# 5_Digitrol.net
KiCad netlist of a schematic drawn in Altium Designer
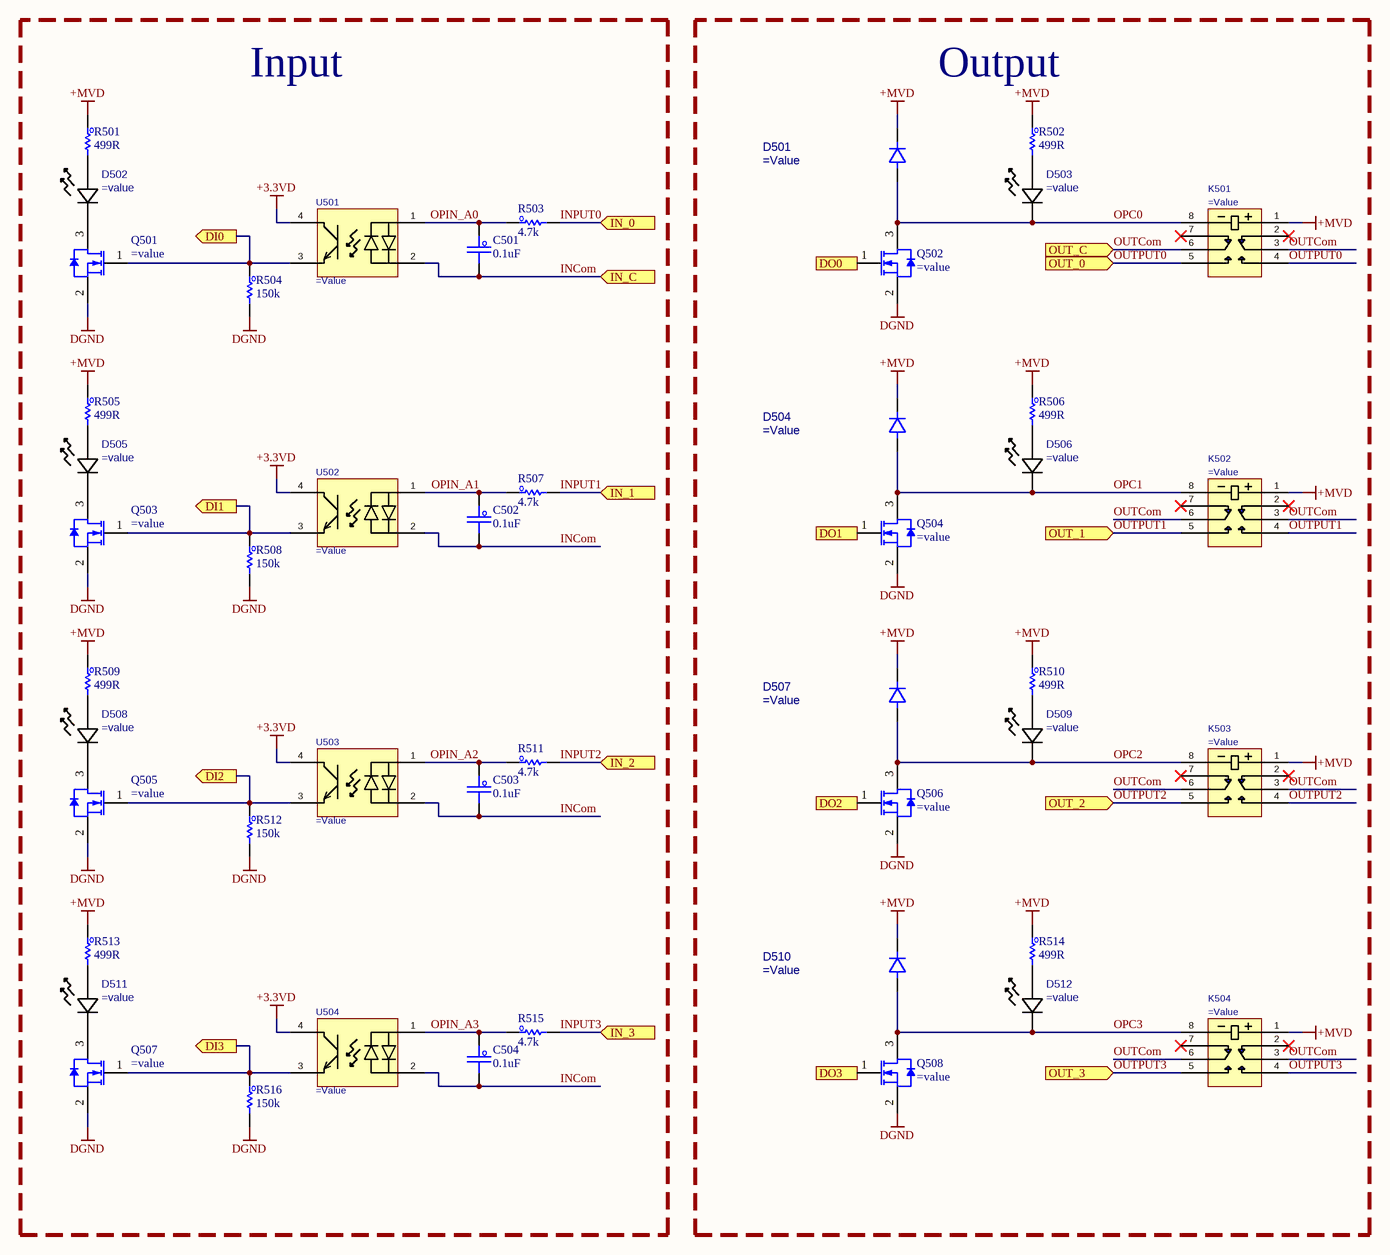
[diagram p0: 5_Digitrol.SchDoc]

(export (version "E")
  (design (tool "Eeschema 10.0.6"))
  (components
    (comp (ref "C501")
      (value "0.1uF")
      (footprint "C_0603")
      (description "CAP CER 0.1UF 50V X7R 0603")
      (fields (field (name "MANUFACTURER") "KEMET") (field (name "PARTNUMBER") "C0603C104K5RACTU"))
      (libsource (lib "UUSymbol") (part "C_Capacitor"))
    )
    (comp (ref "C502")
      (value "0.1uF")
      (footprint "C_0603")
      (description "CAP CER 0.1UF 50V X7R 0603")
      (fields (field (name "MANUFACTURER") "KEMET") (field (name "PARTNUMBER") "C0603C104K5RACTU"))
      (libsource (lib "UUSymbol") (part "C_Capacitor"))
    )
    (comp (ref "C503")
      (value "0.1uF")
      (footprint "C_0603")
      (description "CAP CER 0.1UF 50V X7R 0603")
      (fields (field (name "MANUFACTURER") "KEMET") (field (name "PARTNUMBER") "C0603C104K5RACTU"))
      (libsource (lib "UUSymbol") (part "C_Capacitor"))
    )
    (comp (ref "C504")
      (value "0.1uF")
      (footprint "C_0603")
      (description "CAP CER 0.1UF 50V X7R 0603")
      (fields (field (name "MANUFACTURER") "KEMET") (field (name "PARTNUMBER") "C0603C104K5RACTU"))
      (libsource (lib "UUSymbol") (part "C_Capacitor"))
    )
    (comp (ref "D501")
      (value "~")
      (footprint "DFN119P160X30-2M")
      (description "DIODE SCHOTTKY 30V 2A 0603")
      (fields
        (field (name "MANUFACTURER") "Vishay General Semiconductor - Diodes Division")
        (field (name "PARTNUMBER") "VSKY20301608-G4-08")
      )
      (libsource (lib "UUSymbol") (part "D_PW_VSKY20301608"))
    )
    (comp (ref "D502")
      (value "~")
      (footprint "LED_0VS75000_WRE")
      (description "LED BLUE CLEAR 0603 SMD")
      (fields (field (name "MANUFACTURER") "Wurth Electronics") (field (name "PARTNUMBER") "150060VS75000"))
      (libsource (lib "UUSymbol") (part "D_LED_150060BS75000"))
    )
    (comp (ref "D503")
      (value "~")
      (footprint "LED_0VS75000_WRE")
      (description "LED BLUE CLEAR 0603 SMD")
      (fields (field (name "MANUFACTURER") "Wurth Electronics") (field (name "PARTNUMBER") "150060VS75000"))
      (libsource (lib "UUSymbol") (part "D_LED_150060BS75000"))
    )
    (comp (ref "D504")
      (value "~")
      (footprint "DFN119P160X30-2M")
      (description "DIODE SCHOTTKY 30V 2A 0603")
      (fields
        (field (name "MANUFACTURER") "Vishay General Semiconductor - Diodes Division")
        (field (name "PARTNUMBER") "VSKY20301608-G4-08")
      )
      (libsource (lib "UUSymbol") (part "D_PW_VSKY20301608"))
    )
    (comp (ref "D505")
      (value "~")
      (footprint "LED_0VS75000_WRE")
      (description "LED BLUE CLEAR 0603 SMD")
      (fields (field (name "MANUFACTURER") "Wurth Electronics") (field (name "PARTNUMBER") "150060VS75000"))
      (libsource (lib "UUSymbol") (part "D_LED_150060BS75000"))
    )
    (comp (ref "D506")
      (value "~")
      (footprint "LED_0VS75000_WRE")
      (description "LED BLUE CLEAR 0603 SMD")
      (fields (field (name "MANUFACTURER") "Wurth Electronics") (field (name "PARTNUMBER") "150060VS75000"))
      (libsource (lib "UUSymbol") (part "D_LED_150060BS75000"))
    )
    (comp (ref "D507")
      (value "~")
      (footprint "DFN119P160X30-2M")
      (description "DIODE SCHOTTKY 30V 2A 0603")
      (fields
        (field (name "MANUFACTURER") "Vishay General Semiconductor - Diodes Division")
        (field (name "PARTNUMBER") "VSKY20301608-G4-08")
      )
      (libsource (lib "UUSymbol") (part "D_PW_VSKY20301608"))
    )
    (comp (ref "D508")
      (value "~")
      (footprint "LED_0VS75000_WRE")
      (description "LED BLUE CLEAR 0603 SMD")
      (fields (field (name "MANUFACTURER") "Wurth Electronics") (field (name "PARTNUMBER") "150060VS75000"))
      (libsource (lib "UUSymbol") (part "D_LED_150060BS75000"))
    )
    (comp (ref "D509")
      (value "~")
      (footprint "LED_0VS75000_WRE")
      (description "LED BLUE CLEAR 0603 SMD")
      (fields (field (name "MANUFACTURER") "Wurth Electronics") (field (name "PARTNUMBER") "150060VS75000"))
      (libsource (lib "UUSymbol") (part "D_LED_150060BS75000"))
    )
    (comp (ref "D510")
      (value "~")
      (footprint "DFN119P160X30-2M")
      (description "DIODE SCHOTTKY 30V 2A 0603")
      (fields
        (field (name "MANUFACTURER") "Vishay General Semiconductor - Diodes Division")
        (field (name "PARTNUMBER") "VSKY20301608-G4-08")
      )
      (libsource (lib "UUSymbol") (part "D_PW_VSKY20301608"))
    )
    (comp (ref "D511")
      (value "~")
      (footprint "LED_0VS75000_WRE")
      (description "LED BLUE CLEAR 0603 SMD")
      (fields (field (name "MANUFACTURER") "Wurth Electronics") (field (name "PARTNUMBER") "150060VS75000"))
      (libsource (lib "UUSymbol") (part "D_LED_150060BS75000"))
    )
    (comp (ref "D512")
      (value "~")
      (footprint "LED_0VS75000_WRE")
      (description "LED BLUE CLEAR 0603 SMD")
      (fields (field (name "MANUFACTURER") "Wurth Electronics") (field (name "PARTNUMBER") "150060VS75000"))
      (libsource (lib "UUSymbol") (part "D_LED_150060BS75000"))
    )
    (comp (ref "K501")
      (value "~")
      (footprint "RELAY_HFD4/12-SR")
      (description "Telecom Non Latching 12VDC DPDT SMD Relays RoHS")
      (fields
        (field (name "MANUFACTURER") "Xiamen Hongfa Electroacoustic")
        (field (name "PARTNUMBER") "HFD4/5-SR")
      )
      (libsource (lib "UUSymbol") (part "SW_RELAY_HFD4/12-SR"))
    )
    (comp (ref "K502")
      (value "~")
      (footprint "RELAY_HFD4/12-SR")
      (description "Telecom Non Latching 12VDC DPDT SMD Relays RoHS")
      (fields
        (field (name "MANUFACTURER") "Xiamen Hongfa Electroacoustic")
        (field (name "PARTNUMBER") "HFD4/5-SR")
      )
      (libsource (lib "UUSymbol") (part "SW_RELAY_HFD4/12-SR"))
    )
    (comp (ref "K503")
      (value "~")
      (footprint "RELAY_HFD4/12-SR")
      (description "Telecom Non Latching 12VDC DPDT SMD Relays RoHS")
      (fields
        (field (name "MANUFACTURER") "Xiamen Hongfa Electroacoustic")
        (field (name "PARTNUMBER") "HFD4/5-SR")
      )
      (libsource (lib "UUSymbol") (part "SW_RELAY_HFD4/12-SR"))
    )
    (comp (ref "K504")
      (value "~")
      (footprint "RELAY_HFD4/12-SR")
      (description "Telecom Non Latching 12VDC DPDT SMD Relays RoHS")
      (fields
        (field (name "MANUFACTURER") "Xiamen Hongfa Electroacoustic")
        (field (name "PARTNUMBER") "HFD4/5-SR")
      )
      (libsource (lib "UUSymbol") (part "SW_RELAY_HFD4/12-SR"))
    )
    (comp (ref "Q501")
      (value "~")
      (footprint "SOT95P245X110-3M")
      (description "MOSFET N-CH 60V 300MA SOT23-3")
      (fields
        (field (name "MANUFACTURER") "Infineon Technologies")
        (field (name "PARTNUMBER") "2N7002H6327XTSA2")
      )
      (libsource (lib "UUSymbol") (part "Q_NMOS_2N7002H"))
    )
    (comp (ref "Q502")
      (value "~")
      (footprint "SOT95P245X110-3M")
      (description "MOSFET N-CH 60V 300MA SOT23-3")
      (fields
        (field (name "MANUFACTURER") "Infineon Technologies")
        (field (name "PARTNUMBER") "2N7002H6327XTSA2")
      )
      (libsource (lib "UUSymbol") (part "Q_NMOS_2N7002H"))
    )
    (comp (ref "Q503")
      (value "~")
      (footprint "SOT95P245X110-3M")
      (description "MOSFET N-CH 60V 300MA SOT23-3")
      (fields
        (field (name "MANUFACTURER") "Infineon Technologies")
        (field (name "PARTNUMBER") "2N7002H6327XTSA2")
      )
      (libsource (lib "UUSymbol") (part "Q_NMOS_2N7002H"))
    )
    (comp (ref "Q504")
      (value "~")
      (footprint "SOT95P245X110-3M")
      (description "MOSFET N-CH 60V 300MA SOT23-3")
      (fields
        (field (name "MANUFACTURER") "Infineon Technologies")
        (field (name "PARTNUMBER") "2N7002H6327XTSA2")
      )
      (libsource (lib "UUSymbol") (part "Q_NMOS_2N7002H"))
    )
    (comp (ref "Q505")
      (value "~")
      (footprint "SOT95P245X110-3M")
      (description "MOSFET N-CH 60V 300MA SOT23-3")
      (fields
        (field (name "MANUFACTURER") "Infineon Technologies")
        (field (name "PARTNUMBER") "2N7002H6327XTSA2")
      )
      (libsource (lib "UUSymbol") (part "Q_NMOS_2N7002H"))
    )
    (comp (ref "Q506")
      (value "~")
      (footprint "SOT95P245X110-3M")
      (description "MOSFET N-CH 60V 300MA SOT23-3")
      (fields
        (field (name "MANUFACTURER") "Infineon Technologies")
        (field (name "PARTNUMBER") "2N7002H6327XTSA2")
      )
      (libsource (lib "UUSymbol") (part "Q_NMOS_2N7002H"))
    )
    (comp (ref "Q507")
      (value "~")
      (footprint "SOT95P245X110-3M")
      (description "MOSFET N-CH 60V 300MA SOT23-3")
      (fields
        (field (name "MANUFACTURER") "Infineon Technologies")
        (field (name "PARTNUMBER") "2N7002H6327XTSA2")
      )
      (libsource (lib "UUSymbol") (part "Q_NMOS_2N7002H"))
    )
    (comp (ref "Q508")
      (value "~")
      (footprint "SOT95P245X110-3M")
      (description "MOSFET N-CH 60V 300MA SOT23-3")
      (fields
        (field (name "MANUFACTURER") "Infineon Technologies")
        (field (name "PARTNUMBER") "2N7002H6327XTSA2")
      )
      (libsource (lib "UUSymbol") (part "Q_NMOS_2N7002H"))
    )
    (comp (ref "R501")
      (value "499R")
      (footprint "R_0603")
      (description "RES 499 OHM 1% 1/10W 0603")
      (fields (field (name "MANUFACTURER") "Vishay Dale") (field (name "PARTNUMBER") "CRCW0603499RFKEAC"))
      (libsource (lib "UUSymbol") (part "R_Resister"))
    )
    (comp (ref "R502")
      (value "499R")
      (footprint "R_0603")
      (description "RES 499 OHM 1% 1/10W 0603")
      (fields (field (name "MANUFACTURER") "Vishay Dale") (field (name "PARTNUMBER") "CRCW0603499RFKEAC"))
      (libsource (lib "UUSymbol") (part "R_Resister"))
    )
    (comp (ref "R503")
      (value "4.7k")
      (footprint "R_0603")
      (description "RES 4.7K OHM 5% 1/10W 0603")
      (fields (field (name "MANUFACTURER") "Vishay Dale") (field (name "PARTNUMBER") "CRCW06034K70JNEBC"))
      (libsource (lib "UUSymbol") (part "R_Resister"))
    )
    (comp (ref "R504")
      (value "150k")
      (footprint "R_0603")
      (description "RES SMD 150K OHM 1% 1/10W 0603")
      (fields (field (name "MANUFACTURER") "Vishay Dale") (field (name "PARTNUMBER") "CRCW0603150KFKEAC"))
      (libsource (lib "UUSymbol") (part "R_Resister"))
    )
    (comp (ref "R505")
      (value "499R")
      (footprint "R_0603")
      (description "RES 499 OHM 1% 1/10W 0603")
      (fields (field (name "MANUFACTURER") "Vishay Dale") (field (name "PARTNUMBER") "CRCW0603499RFKEAC"))
      (libsource (lib "UUSymbol") (part "R_Resister"))
    )
    (comp (ref "R506")
      (value "499R")
      (footprint "R_0603")
      (description "RES 499 OHM 1% 1/10W 0603")
      (fields (field (name "MANUFACTURER") "Vishay Dale") (field (name "PARTNUMBER") "CRCW0603499RFKEAC"))
      (libsource (lib "UUSymbol") (part "R_Resister"))
    )
    (comp (ref "R507")
      (value "4.7k")
      (footprint "R_0603")
      (description "RES 4.7K OHM 5% 1/10W 0603")
      (fields (field (name "MANUFACTURER") "Vishay Dale") (field (name "PARTNUMBER") "CRCW06034K70JNEBC"))
      (libsource (lib "UUSymbol") (part "R_Resister"))
    )
    (comp (ref "R508")
      (value "150k")
      (footprint "R_0603")
      (description "RES SMD 150K OHM 1% 1/10W 0603")
      (fields (field (name "MANUFACTURER") "Vishay Dale") (field (name "PARTNUMBER") "CRCW0603150KFKEAC"))
      (libsource (lib "UUSymbol") (part "R_Resister"))
    )
    (comp (ref "R509")
      (value "499R")
      (footprint "R_0603")
      (description "RES 499 OHM 1% 1/10W 0603")
      (fields (field (name "MANUFACTURER") "Vishay Dale") (field (name "PARTNUMBER") "CRCW0603499RFKEAC"))
      (libsource (lib "UUSymbol") (part "R_Resister"))
    )
    (comp (ref "R510")
      (value "499R")
      (footprint "R_0603")
      (description "RES 499 OHM 1% 1/10W 0603")
      (fields (field (name "MANUFACTURER") "Vishay Dale") (field (name "PARTNUMBER") "CRCW0603499RFKEAC"))
      (libsource (lib "UUSymbol") (part "R_Resister"))
    )
    (comp (ref "R511")
      (value "4.7k")
      (footprint "R_0603")
      (description "RES 4.7K OHM 5% 1/10W 0603")
      (fields (field (name "MANUFACTURER") "Vishay Dale") (field (name "PARTNUMBER") "CRCW06034K70JNEBC"))
      (libsource (lib "UUSymbol") (part "R_Resister"))
    )
    (comp (ref "R512")
      (value "150k")
      (footprint "R_0603")
      (description "RES SMD 150K OHM 1% 1/10W 0603")
      (fields (field (name "MANUFACTURER") "Vishay Dale") (field (name "PARTNUMBER") "CRCW0603150KFKEAC"))
      (libsource (lib "UUSymbol") (part "R_Resister"))
    )
    (comp (ref "R513")
      (value "499R")
      (footprint "R_0603")
      (description "RES 499 OHM 1% 1/10W 0603")
      (fields (field (name "MANUFACTURER") "Vishay Dale") (field (name "PARTNUMBER") "CRCW0603499RFKEAC"))
      (libsource (lib "UUSymbol") (part "R_Resister"))
    )
    (comp (ref "R514")
      (value "499R")
      (footprint "R_0603")
      (description "RES 499 OHM 1% 1/10W 0603")
      (fields (field (name "MANUFACTURER") "Vishay Dale") (field (name "PARTNUMBER") "CRCW0603499RFKEAC"))
      (libsource (lib "UUSymbol") (part "R_Resister"))
    )
    (comp (ref "R515")
      (value "4.7k")
      (footprint "R_0603")
      (description "RES 4.7K OHM 5% 1/10W 0603")
      (fields (field (name "MANUFACTURER") "Vishay Dale") (field (name "PARTNUMBER") "CRCW06034K70JNEBC"))
      (libsource (lib "UUSymbol") (part "R_Resister"))
    )
    (comp (ref "R516")
      (value "150k")
      (footprint "R_0603")
      (description "RES SMD 150K OHM 1% 1/10W 0603")
      (fields (field (name "MANUFACTURER") "Vishay Dale") (field (name "PARTNUMBER") "CRCW0603150KFKEAC"))
      (libsource (lib "UUSymbol") (part "R_Resister"))
    )
    (comp (ref "U501")
      (value "~")
      (footprint "LTV-814S_LTO")
      (description "OPTOISOLATR 5KV TRANSISTOR 4-SMD")
      (fields (field (name "MANUFACTURER") "Lite-On Inc.") (field (name "PARTNUMBER") "LTV-814S-TA1"))
      (libsource (lib "UUSymbol") (part "IC_OPTO_LTV-814S-TA1"))
    )
    (comp (ref "U502")
      (value "~")
      (footprint "LTV-814S_LTO")
      (description "OPTOISOLATR 5KV TRANSISTOR 4-SMD")
      (fields (field (name "MANUFACTURER") "Lite-On Inc.") (field (name "PARTNUMBER") "LTV-814S-TA1"))
      (libsource (lib "UUSymbol") (part "IC_OPTO_LTV-814S-TA1"))
    )
    (comp (ref "U503")
      (value "~")
      (footprint "LTV-814S_LTO")
      (description "OPTOISOLATR 5KV TRANSISTOR 4-SMD")
      (fields (field (name "MANUFACTURER") "Lite-On Inc.") (field (name "PARTNUMBER") "LTV-814S-TA1"))
      (libsource (lib "UUSymbol") (part "IC_OPTO_LTV-814S-TA1"))
    )
    (comp (ref "U504")
      (value "~")
      (footprint "LTV-814S_LTO")
      (description "OPTOISOLATR 5KV TRANSISTOR 4-SMD")
      (fields (field (name "MANUFACTURER") "Lite-On Inc.") (field (name "PARTNUMBER") "LTV-814S-TA1"))
      (libsource (lib "UUSymbol") (part "IC_OPTO_LTV-814S-TA1"))
    )
  )
  (nets
    (net (code "1") (name "+3.3VD") (class "Default")
      (node (ref "U501") (pin "4") (pinfunction "C_4") (pintype "passive"))
      (node (ref "U502") (pin "4") (pinfunction "C_4") (pintype "passive"))
      (node (ref "U503") (pin "4") (pinfunction "C_4") (pintype "passive"))
      (node (ref "U504") (pin "4") (pinfunction "C_4") (pintype "passive"))
    )
    (net (code "2") (name "+MVD") (class "Default")
      (node (ref "D501") (pin "1") (pinfunction "1_1") (pintype "passive"))
      (node (ref "D504") (pin "1") (pinfunction "1_1") (pintype "passive"))
      (node (ref "D507") (pin "1") (pinfunction "1_1") (pintype "passive"))
      (node (ref "D510") (pin "1") (pinfunction "1_1") (pintype "passive"))
      (node (ref "K501") (pin "1") (pinfunction "1_1") (pintype "passive"))
      (node (ref "K502") (pin "1") (pinfunction "1_1") (pintype "passive"))
      (node (ref "K503") (pin "1") (pinfunction "1_1") (pintype "passive"))
      (node (ref "K504") (pin "1") (pinfunction "1_1") (pintype "passive"))
      (node (ref "R501") (pin "1") (pinfunction "1_1") (pintype "passive"))
      (node (ref "R502") (pin "1") (pinfunction "1_1") (pintype "passive"))
      (node (ref "R505") (pin "1") (pinfunction "1_1") (pintype "passive"))
      (node (ref "R506") (pin "1") (pinfunction "1_1") (pintype "passive"))
      (node (ref "R509") (pin "1") (pinfunction "1_1") (pintype "passive"))
      (node (ref "R510") (pin "1") (pinfunction "1_1") (pintype "passive"))
      (node (ref "R513") (pin "1") (pinfunction "1_1") (pintype "passive"))
      (node (ref "R514") (pin "1") (pinfunction "1_1") (pintype "passive"))
    )
    (net (code "3") (name "/DI0") (class "Default")
      (node (ref "Q501") (pin "1") (pinfunction "G_1") (pintype "passive"))
      (node (ref "R504") (pin "1") (pinfunction "1_1") (pintype "passive"))
      (node (ref "U501") (pin "3") (pinfunction "E_3") (pintype "passive"))
    )
    (net (code "4") (name "/DI1") (class "Default")
      (node (ref "Q503") (pin "1") (pinfunction "G_1") (pintype "passive"))
      (node (ref "R508") (pin "1") (pinfunction "1_1") (pintype "passive"))
      (node (ref "U502") (pin "3") (pinfunction "E_3") (pintype "passive"))
    )
    (net (code "5") (name "/DI2") (class "Default")
      (node (ref "Q505") (pin "1") (pinfunction "G_1") (pintype "passive"))
      (node (ref "R512") (pin "1") (pinfunction "1_1") (pintype "passive"))
      (node (ref "U503") (pin "3") (pinfunction "E_3") (pintype "passive"))
    )
    (net (code "6") (name "/DI3") (class "Default")
      (node (ref "Q507") (pin "1") (pinfunction "G_1") (pintype "passive"))
      (node (ref "R516") (pin "1") (pinfunction "1_1") (pintype "passive"))
      (node (ref "U504") (pin "3") (pinfunction "E_3") (pintype "passive"))
    )
    (net (code "7") (name "/DO0") (class "Default")
      (node (ref "Q502") (pin "1") (pinfunction "G_1") (pintype "passive"))
    )
    (net (code "8") (name "/DO1") (class "Default")
      (node (ref "Q504") (pin "1") (pinfunction "G_1") (pintype "passive"))
    )
    (net (code "9") (name "/DO2") (class "Default")
      (node (ref "Q506") (pin "1") (pinfunction "G_1") (pintype "passive"))
    )
    (net (code "10") (name "/DO3") (class "Default")
      (node (ref "Q508") (pin "1") (pinfunction "G_1") (pintype "passive"))
    )
    (net (code "11") (name "/INCom") (class "Default")
      (node (ref "C501") (pin "2") (pinfunction "2_2") (pintype "passive"))
      (node (ref "C502") (pin "2") (pinfunction "2_2") (pintype "passive"))
      (node (ref "C503") (pin "2") (pinfunction "2_2") (pintype "passive"))
      (node (ref "C504") (pin "2") (pinfunction "2_2") (pintype "passive"))
      (node (ref "U501") (pin "2") (pinfunction "C_2_2") (pintype "passive"))
      (node (ref "U502") (pin "2") (pinfunction "C_2_2") (pintype "passive"))
      (node (ref "U503") (pin "2") (pinfunction "C_2_2") (pintype "passive"))
      (node (ref "U504") (pin "2") (pinfunction "C_2_2") (pintype "passive"))
    )
    (net (code "12") (name "/INPUT0") (class "Default")
      (node (ref "R503") (pin "2") (pinfunction "2_2") (pintype "passive"))
    )
    (net (code "13") (name "/INPUT1") (class "Default")
      (node (ref "R507") (pin "2") (pinfunction "2_2") (pintype "passive"))
    )
    (net (code "14") (name "/INPUT2") (class "Default")
      (node (ref "R511") (pin "2") (pinfunction "2_2") (pintype "passive"))
    )
    (net (code "15") (name "/INPUT3") (class "Default")
      (node (ref "R515") (pin "2") (pinfunction "2_2") (pintype "passive"))
    )
    (net (code "16") (name "/OPC0") (class "Default")
      (node (ref "D501") (pin "2") (pinfunction "2_2") (pintype "passive"))
      (node (ref "D503") (pin "1") (pinfunction "1_1") (pintype "passive"))
      (node (ref "K501") (pin "8") (pinfunction "8_8") (pintype "passive"))
      (node (ref "Q502") (pin "3") (pinfunction "D_3") (pintype "passive"))
    )
    (net (code "17") (name "/OPC1") (class "Default")
      (node (ref "D504") (pin "2") (pinfunction "2_2") (pintype "passive"))
      (node (ref "D506") (pin "1") (pinfunction "1_1") (pintype "passive"))
      (node (ref "K502") (pin "8") (pinfunction "8_8") (pintype "passive"))
      (node (ref "Q504") (pin "3") (pinfunction "D_3") (pintype "passive"))
    )
    (net (code "18") (name "/OPC2") (class "Default")
      (node (ref "D507") (pin "2") (pinfunction "2_2") (pintype "passive"))
      (node (ref "D509") (pin "1") (pinfunction "1_1") (pintype "passive"))
      (node (ref "K503") (pin "8") (pinfunction "8_8") (pintype "passive"))
      (node (ref "Q506") (pin "3") (pinfunction "D_3") (pintype "passive"))
    )
    (net (code "19") (name "/OPC3") (class "Default")
      (node (ref "D510") (pin "2") (pinfunction "2_2") (pintype "passive"))
      (node (ref "D512") (pin "1") (pinfunction "1_1") (pintype "passive"))
      (node (ref "K504") (pin "8") (pinfunction "8_8") (pintype "passive"))
      (node (ref "Q508") (pin "3") (pinfunction "D_3") (pintype "passive"))
    )
    (net (code "20") (name "/OPIN_A0") (class "Default")
      (node (ref "C501") (pin "1") (pinfunction "1_1") (pintype "passive"))
      (node (ref "R503") (pin "1") (pinfunction "1_1") (pintype "passive"))
      (node (ref "U501") (pin "1") (pinfunction "A_1") (pintype "passive"))
    )
    (net (code "21") (name "/OPIN_A1") (class "Default")
      (node (ref "C502") (pin "1") (pinfunction "1_1") (pintype "passive"))
      (node (ref "R507") (pin "1") (pinfunction "1_1") (pintype "passive"))
      (node (ref "U502") (pin "1") (pinfunction "A_1") (pintype "passive"))
    )
    (net (code "22") (name "/OPIN_A2") (class "Default")
      (node (ref "C503") (pin "1") (pinfunction "1_1") (pintype "passive"))
      (node (ref "R511") (pin "1") (pinfunction "1_1") (pintype "passive"))
      (node (ref "U503") (pin "1") (pinfunction "A_1") (pintype "passive"))
    )
    (net (code "23") (name "/OPIN_A3") (class "Default")
      (node (ref "C504") (pin "1") (pinfunction "1_1") (pintype "passive"))
      (node (ref "R515") (pin "1") (pinfunction "1_1") (pintype "passive"))
      (node (ref "U504") (pin "1") (pinfunction "A_1") (pintype "passive"))
    )
    (net (code "24") (name "/OUTCom") (class "Default")
      (node (ref "K501") (pin "3") (pinfunction "3_3") (pintype "passive"))
      (node (ref "K501") (pin "6") (pinfunction "6_6") (pintype "passive"))
      (node (ref "K502") (pin "3") (pinfunction "3_3") (pintype "passive"))
      (node (ref "K502") (pin "6") (pinfunction "6_6") (pintype "passive"))
      (node (ref "K503") (pin "3") (pinfunction "3_3") (pintype "passive"))
      (node (ref "K503") (pin "6") (pinfunction "6_6") (pintype "passive"))
      (node (ref "K504") (pin "3") (pinfunction "3_3") (pintype "passive"))
      (node (ref "K504") (pin "6") (pinfunction "6_6") (pintype "passive"))
    )
    (net (code "25") (name "/OUTPUT0") (class "Default")
      (node (ref "K501") (pin "4") (pinfunction "4_4") (pintype "passive"))
      (node (ref "K501") (pin "5") (pinfunction "5_5") (pintype "passive"))
    )
    (net (code "26") (name "/OUTPUT1") (class "Default")
      (node (ref "K502") (pin "4") (pinfunction "4_4") (pintype "passive"))
      (node (ref "K502") (pin "5") (pinfunction "5_5") (pintype "passive"))
    )
    (net (code "27") (name "/OUTPUT2") (class "Default")
      (node (ref "K503") (pin "4") (pinfunction "4_4") (pintype "passive"))
      (node (ref "K503") (pin "5") (pinfunction "5_5") (pintype "passive"))
    )
    (net (code "28") (name "/OUTPUT3") (class "Default")
      (node (ref "K504") (pin "4") (pinfunction "4_4") (pintype "passive"))
      (node (ref "K504") (pin "5") (pinfunction "5_5") (pintype "passive"))
    )
    (net (code "29") (name "DGND") (class "Default")
      (node (ref "Q501") (pin "2") (pinfunction "S_2") (pintype "passive"))
      (node (ref "Q502") (pin "2") (pinfunction "S_2") (pintype "passive"))
      (node (ref "Q503") (pin "2") (pinfunction "S_2") (pintype "passive"))
      (node (ref "Q504") (pin "2") (pinfunction "S_2") (pintype "passive"))
      (node (ref "Q505") (pin "2") (pinfunction "S_2") (pintype "passive"))
      (node (ref "Q506") (pin "2") (pinfunction "S_2") (pintype "passive"))
      (node (ref "Q507") (pin "2") (pinfunction "S_2") (pintype "passive"))
      (node (ref "Q508") (pin "2") (pinfunction "S_2") (pintype "passive"))
      (node (ref "R504") (pin "2") (pinfunction "2_2") (pintype "passive"))
      (node (ref "R508") (pin "2") (pinfunction "2_2") (pintype "passive"))
      (node (ref "R512") (pin "2") (pinfunction "2_2") (pintype "passive"))
      (node (ref "R516") (pin "2") (pinfunction "2_2") (pintype "passive"))
    )
    (net (code "30") (name "Net-(D502-Pad2)") (class "Default")
      (node (ref "D502") (pin "2") (pinfunction "2_2") (pintype "passive"))
      (node (ref "R501") (pin "2") (pinfunction "2_2") (pintype "passive"))
    )
    (net (code "31") (name "Net-(D503-Pad2)") (class "Default")
      (node (ref "D503") (pin "2") (pinfunction "2_2") (pintype "passive"))
      (node (ref "R502") (pin "2") (pinfunction "2_2") (pintype "passive"))
    )
    (net (code "32") (name "Net-(D505-Pad2)") (class "Default")
      (node (ref "D505") (pin "2") (pinfunction "2_2") (pintype "passive"))
      (node (ref "R505") (pin "2") (pinfunction "2_2") (pintype "passive"))
    )
    (net (code "33") (name "Net-(D506-Pad2)") (class "Default")
      (node (ref "D506") (pin "2") (pinfunction "2_2") (pintype "passive"))
      (node (ref "R506") (pin "2") (pinfunction "2_2") (pintype "passive"))
    )
    (net (code "34") (name "Net-(D508-Pad2)") (class "Default")
      (node (ref "D508") (pin "2") (pinfunction "2_2") (pintype "passive"))
      (node (ref "R509") (pin "2") (pinfunction "2_2") (pintype "passive"))
    )
    (net (code "35") (name "Net-(D509-Pad2)") (class "Default")
      (node (ref "D509") (pin "2") (pinfunction "2_2") (pintype "passive"))
      (node (ref "R510") (pin "2") (pinfunction "2_2") (pintype "passive"))
    )
    (net (code "36") (name "Net-(D511-Pad2)") (class "Default")
      (node (ref "D511") (pin "2") (pinfunction "2_2") (pintype "passive"))
      (node (ref "R513") (pin "2") (pinfunction "2_2") (pintype "passive"))
    )
    (net (code "37") (name "Net-(D512-Pad2)") (class "Default")
      (node (ref "D512") (pin "2") (pinfunction "2_2") (pintype "passive"))
      (node (ref "R514") (pin "2") (pinfunction "2_2") (pintype "passive"))
    )
    (net (code "38") (name "Net-(Q501-D)") (class "Default")
      (node (ref "D502") (pin "1") (pinfunction "1_1") (pintype "passive"))
      (node (ref "Q501") (pin "3") (pinfunction "D_3") (pintype "passive"))
    )
    (net (code "39") (name "Net-(Q503-D)") (class "Default")
      (node (ref "D505") (pin "1") (pinfunction "1_1") (pintype "passive"))
      (node (ref "Q503") (pin "3") (pinfunction "D_3") (pintype "passive"))
    )
    (net (code "40") (name "Net-(Q505-D)") (class "Default")
      (node (ref "D508") (pin "1") (pinfunction "1_1") (pintype "passive"))
      (node (ref "Q505") (pin "3") (pinfunction "D_3") (pintype "passive"))
    )
    (net (code "41") (name "Net-(Q507-D)") (class "Default")
      (node (ref "D511") (pin "1") (pinfunction "1_1") (pintype "passive"))
      (node (ref "Q507") (pin "3") (pinfunction "D_3") (pintype "passive"))
    )
    (net (code "42") (name "unconnected-(K501-Pad2)") (class "Default")
      (node (ref "K501") (pin "2") (pinfunction "2_2") (pintype "passive+no_connect"))
    )
    (net (code "43") (name "unconnected-(K501-Pad7)") (class "Default")
      (node (ref "K501") (pin "7") (pinfunction "7_7") (pintype "passive+no_connect"))
    )
    (net (code "44") (name "unconnected-(K502-Pad2)") (class "Default")
      (node (ref "K502") (pin "2") (pinfunction "2_2") (pintype "passive+no_connect"))
    )
    (net (code "45") (name "unconnected-(K502-Pad7)") (class "Default")
      (node (ref "K502") (pin "7") (pinfunction "7_7") (pintype "passive+no_connect"))
    )
    (net (code "46") (name "unconnected-(K503-Pad2)") (class "Default")
      (node (ref "K503") (pin "2") (pinfunction "2_2") (pintype "passive+no_connect"))
    )
    (net (code "47") (name "unconnected-(K503-Pad7)") (class "Default")
      (node (ref "K503") (pin "7") (pinfunction "7_7") (pintype "passive+no_connect"))
    )
    (net (code "48") (name "unconnected-(K504-Pad2)") (class "Default")
      (node (ref "K504") (pin "2") (pinfunction "2_2") (pintype "passive+no_connect"))
    )
    (net (code "49") (name "unconnected-(K504-Pad7)") (class "Default")
      (node (ref "K504") (pin "7") (pinfunction "7_7") (pintype "passive+no_connect"))
    )
  )
)
